# ADS7946.net
KiCad netlist of a schematic drawn in Altium Designer
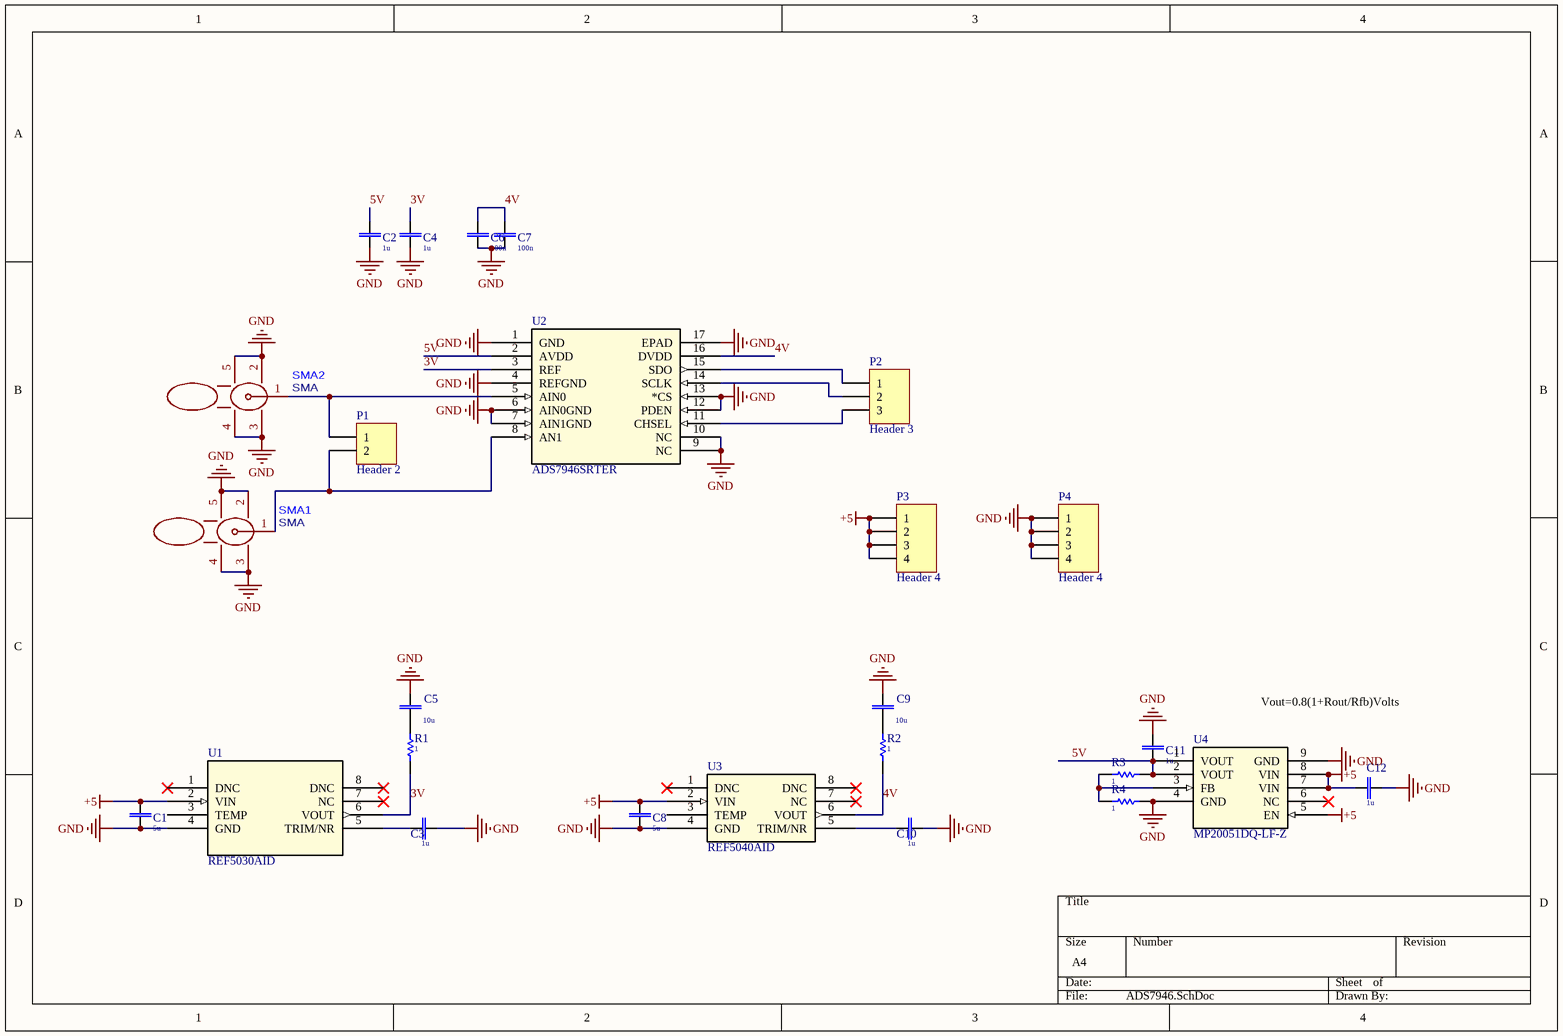
[diagram p0: ADS7946.SchDoc]

(export (version "E")
  (design (tool "Eeschema 10.0.6"))
  (components
    (comp (ref "C1")
      (value "5u")
      (footprint "0603")
      (description "Capacitor")
      (fields (field (name "Comment") "Cap") (field (name "PUBLISHER") "Altium Limited"))
      (libsource (lib "Miscellaneous Devices") (part "Cap"))
    )
    (comp (ref "C2")
      (value "1u")
      (footprint "0603")
      (description "Capacitor")
      (fields (field (name "Comment") "Cap") (field (name "PUBLISHER") "Altium Limited"))
      (libsource (lib "Miscellaneous Devices") (part "Cap"))
    )
    (comp (ref "C3")
      (value "1u")
      (footprint "0603")
      (description "Capacitor")
      (fields (field (name "Comment") "Cap") (field (name "PUBLISHER") "Altium Limited"))
      (libsource (lib "Miscellaneous Devices") (part "Cap"))
    )
    (comp (ref "C4")
      (value "1u")
      (footprint "0603")
      (description "Capacitor")
      (fields (field (name "Comment") "Cap") (field (name "PUBLISHER") "Altium Limited"))
      (libsource (lib "Miscellaneous Devices") (part "Cap"))
    )
    (comp (ref "C5")
      (value "10u")
      (footprint "0603")
      (description "Capacitor")
      (fields (field (name "Comment") "Cap") (field (name "PUBLISHER") "Altium Limited"))
      (libsource (lib "Miscellaneous Devices") (part "Cap"))
    )
    (comp (ref "C6")
      (value "100n")
      (footprint "0603")
      (description "Capacitor")
      (fields (field (name "Comment") "Cap") (field (name "PUBLISHER") "Altium Limited"))
      (libsource (lib "Miscellaneous Devices") (part "Cap"))
    )
    (comp (ref "C7")
      (value "100n")
      (footprint "0603")
      (description "Capacitor")
      (fields (field (name "Comment") "Cap") (field (name "PUBLISHER") "Altium Limited"))
      (libsource (lib "Miscellaneous Devices") (part "Cap"))
    )
    (comp (ref "C8")
      (value "5u")
      (footprint "0603")
      (description "Capacitor")
      (fields (field (name "Comment") "Cap") (field (name "PUBLISHER") "Altium Limited"))
      (libsource (lib "Miscellaneous Devices") (part "Cap"))
    )
    (comp (ref "C9")
      (value "10u")
      (footprint "0603")
      (description "Capacitor")
      (fields (field (name "Comment") "Cap") (field (name "PUBLISHER") "Altium Limited"))
      (libsource (lib "Miscellaneous Devices") (part "Cap"))
    )
    (comp (ref "C10")
      (value "1u")
      (footprint "0603")
      (description "Capacitor")
      (fields (field (name "Comment") "Cap") (field (name "PUBLISHER") "Altium Limited"))
      (libsource (lib "Miscellaneous Devices") (part "Cap"))
    )
    (comp (ref "C11")
      (value "1u")
      (footprint "0603")
      (description "Capacitor")
      (fields (field (name "Comment") "Cap") (field (name "PUBLISHER") "Altium Limited"))
      (libsource (lib "Miscellaneous Devices") (part "Cap"))
    )
    (comp (ref "C12")
      (value "1u")
      (footprint "0603")
      (description "Capacitor")
      (fields (field (name "Comment") "Cap") (field (name "PUBLISHER") "Altium Limited"))
      (libsource (lib "Miscellaneous Devices") (part "Cap"))
    )
    (comp (ref "P1")
      (value "Header 2")
      (footprint "HDR1X2")
      (description "Header, 2-Pin")
      (fields (field (name "PUBLISHER") "Altium Limited"))
      (libsource (lib "Miscellaneous Connectors") (part "Header 2"))
    )
    (comp (ref "P2")
      (value "Header 3")
      (footprint "HDR1X3")
      (description "Header, 3-Pin")
      (fields (field (name "PUBLISHER") "Altium Limited"))
      (libsource (lib "Miscellaneous Connectors") (part "Header 3"))
    )
    (comp (ref "P3")
      (value "Header 4")
      (footprint "HDR1X4")
      (description "Header, 4-Pin")
      (fields (field (name "PUBLISHER") "Altium Limited"))
      (libsource (lib "Miscellaneous Connectors") (part "Header 4"))
    )
    (comp (ref "P4")
      (value "Header 4")
      (footprint "HDR1X4")
      (description "Header, 4-Pin")
      (fields (field (name "PUBLISHER") "Altium Limited"))
      (libsource (lib "Miscellaneous Connectors") (part "Header 4"))
    )
    (comp (ref "R1")
      (value "1")
      (footprint "RES 0805N (2012)")
      (description "Resistor")
      (fields (field (name "PUBLISHER") "Altium Limited"))
      (libsource (lib "Miscellaneous Devices") (part "Res1"))
    )
    (comp (ref "R2")
      (value "1")
      (footprint "RES 0805N (2012)")
      (description "Resistor")
      (fields (field (name "PUBLISHER") "Altium Limited"))
      (libsource (lib "Miscellaneous Devices") (part "Res1"))
    )
    (comp (ref "R3")
      (value "1")
      (footprint "RES 0805N (2012)")
      (description "Resistor")
      (fields (field (name "PUBLISHER") "Altium Limited"))
      (libsource (lib "Miscellaneous Devices") (part "Res1"))
    )
    (comp (ref "R4")
      (value "1")
      (footprint "RES 0805N (2012)")
      (description "Resistor")
      (fields (field (name "PUBLISHER") "Altium Limited"))
      (libsource (lib "Miscellaneous Devices") (part "Res1"))
    )
    (comp (ref "SMA1") (value "SMA") (footprint "SMA-SMD_BWSMA-KE-P001") (libsource (lib "SMA") (part "SMA")))
    (comp (ref "SMA2") (value "SMA") (footprint "SMA-SMD_BWSMA-KE-P001") (libsource (lib "SMA") (part "SMA")))
    (comp (ref "U1")
      (value "REF5030AID")
      (footprint "D8")
      (description "No Description Available")
      (fields (field (name "COPYRIGHT") "Copyright (C) 2022 Ultra Librarian. All rights reserved."))
      (libsource (lib "REF5050AID") (part "REF5030AID"))
    )
    (comp (ref "U2")
      (value "ADS7946SRTER")
      (footprint "RTE16_1P7X1P7")
      (description "No Description Available")
      (fields (field (name "COPYRIGHT") "Copyright (C) 2022 Ultra Librarian. All rights reserved."))
      (libsource (lib "ADS7946SRTER") (part "ADS7946SRTER"))
    )
    (comp (ref "U3")
      (value "REF5040AID")
      (footprint "D8")
      (description "No Description Available")
      (fields (field (name "COPYRIGHT") "Copyright (C) 2022 Ultra Librarian. All rights reserved."))
      (libsource (lib "REF5050AID") (part "REF5040AID"))
    )
    (comp (ref "U4")
      (value "MP20051DQ-LF-Z")
      (footprint "QFN-8_MP20051_MNP")
      (description "No Description Available")
      (fields (field (name "COPYRIGHT") "Copyright (C) 2022 Ultra Librarian. All rights reserved."))
      (libsource (lib "ADS7946SRTER") (part "MP20051DQ-LF-Z"))
    )
  )
  (nets
    (net (code "1") (name "+5") (class "Default")
      (node (ref "C1") (pin "2") (pinfunction "2_2") (pintype "passive"))
      (node (ref "C12") (pin "2") (pinfunction "2_2") (pintype "passive"))
      (node (ref "C8") (pin "2") (pinfunction "2_2") (pintype "passive"))
      (node (ref "P3") (pin "1") (pinfunction "1_1") (pintype "passive"))
      (node (ref "P3") (pin "2") (pinfunction "2_2") (pintype "passive"))
      (node (ref "P3") (pin "3") (pinfunction "3_3") (pintype "passive"))
      (node (ref "P3") (pin "4") (pinfunction "4_4") (pintype "passive"))
      (node (ref "U1") (pin "2") (pinfunction "VIN_2") (pintype "input"))
      (node (ref "U3") (pin "2") (pinfunction "VIN_2") (pintype "input"))
      (node (ref "U4") (pin "5") (pinfunction "EN_5") (pintype "input"))
      (node (ref "U4") (pin "7") (pinfunction "VIN_7") (pintype "power_in"))
      (node (ref "U4") (pin "8") (pinfunction "VIN_8") (pintype "power_in"))
    )
    (net (code "2") (name "/3V") (class "Default")
      (node (ref "C4") (pin "2") (pinfunction "2_2") (pintype "passive"))
      (node (ref "R1") (pin "1") (pinfunction "1_1") (pintype "passive"))
      (node (ref "U1") (pin "6") (pinfunction "VOUT_6") (pintype "output"))
      (node (ref "U2") (pin "3") (pinfunction "REF_3") (pintype "power_in"))
    )
    (net (code "3") (name "/4V") (class "Default")
      (node (ref "C6") (pin "2") (pinfunction "2_2") (pintype "passive"))
      (node (ref "C7") (pin "2") (pinfunction "2_2") (pintype "passive"))
      (node (ref "R2") (pin "1") (pinfunction "1_1") (pintype "passive"))
      (node (ref "U2") (pin "16") (pinfunction "DVDD_16") (pintype "power_in"))
      (node (ref "U3") (pin "6") (pinfunction "VOUT_6") (pintype "output"))
    )
    (net (code "4") (name "/5V") (class "Default")
      (node (ref "C11") (pin "2") (pinfunction "2_2") (pintype "passive"))
      (node (ref "C2") (pin "2") (pinfunction "2_2") (pintype "passive"))
      (node (ref "R3") (pin "1") (pinfunction "1_1") (pintype "passive"))
      (node (ref "U2") (pin "2") (pinfunction "AVDD_2") (pintype "power_in"))
      (node (ref "U4") (pin "1") (pinfunction "VOUT_1") (pintype "power_in"))
      (node (ref "U4") (pin "2") (pinfunction "VOUT_2") (pintype "power_in"))
    )
    (net (code "5") (name "GND") (class "Default")
      (node (ref "C1") (pin "1") (pinfunction "1_1") (pintype "passive"))
      (node (ref "C10") (pin "2") (pinfunction "2_2") (pintype "passive"))
      (node (ref "C11") (pin "1") (pinfunction "1_1") (pintype "passive"))
      (node (ref "C12") (pin "1") (pinfunction "1_1") (pintype "passive"))
      (node (ref "C2") (pin "1") (pinfunction "1_1") (pintype "passive"))
      (node (ref "C3") (pin "2") (pinfunction "2_2") (pintype "passive"))
      (node (ref "C4") (pin "1") (pinfunction "1_1") (pintype "passive"))
      (node (ref "C5") (pin "2") (pinfunction "2_2") (pintype "passive"))
      (node (ref "C6") (pin "1") (pinfunction "1_1") (pintype "passive"))
      (node (ref "C7") (pin "1") (pinfunction "1_1") (pintype "passive"))
      (node (ref "C8") (pin "1") (pinfunction "1_1") (pintype "passive"))
      (node (ref "C9") (pin "2") (pinfunction "2_2") (pintype "passive"))
      (node (ref "P4") (pin "1") (pinfunction "1_1") (pintype "passive"))
      (node (ref "P4") (pin "2") (pinfunction "2_2") (pintype "passive"))
      (node (ref "P4") (pin "3") (pinfunction "3_3") (pintype "passive"))
      (node (ref "P4") (pin "4") (pinfunction "4_4") (pintype "passive"))
      (node (ref "R4") (pin "1") (pinfunction "1_1") (pintype "passive"))
      (node (ref "SMA1") (pin "2") (pinfunction "2_2") (pintype "passive"))
      (node (ref "SMA1") (pin "3") (pinfunction "3_3") (pintype "passive"))
      (node (ref "SMA1") (pin "4") (pinfunction "4_4") (pintype "passive"))
      (node (ref "SMA1") (pin "5") (pinfunction "5_5") (pintype "passive"))
      (node (ref "SMA2") (pin "2") (pinfunction "2_2") (pintype "passive"))
      (node (ref "SMA2") (pin "3") (pinfunction "3_3") (pintype "passive"))
      (node (ref "SMA2") (pin "4") (pinfunction "4_4") (pintype "passive"))
      (node (ref "SMA2") (pin "5") (pinfunction "5_5") (pintype "passive"))
      (node (ref "U1") (pin "4") (pinfunction "GND_4") (pintype "passive"))
      (node (ref "U2") (pin "1") (pinfunction "GND_1") (pintype "power_in"))
      (node (ref "U2") (pin "10") (pinfunction "NC_10") (pintype "passive"))
      (node (ref "U2") (pin "12") (pinfunction "PDEN_12") (pintype "input"))
      (node (ref "U2") (pin "13") (pinfunction "*CS_13") (pintype "input"))
      (node (ref "U2") (pin "17") (pinfunction "EPAD_17") (pintype "power_in"))
      (node (ref "U2") (pin "4") (pinfunction "REFGND_4") (pintype "power_in"))
      (node (ref "U2") (pin "6") (pinfunction "AIN0GND_6") (pintype "input"))
      (node (ref "U2") (pin "7") (pinfunction "AIN1GND_7") (pintype "input"))
      (node (ref "U2") (pin "9") (pinfunction "NC_9") (pintype "passive"))
      (node (ref "U3") (pin "4") (pinfunction "GND_4") (pintype "passive"))
      (node (ref "U4") (pin "4") (pinfunction "GND_4") (pintype "power_in"))
      (node (ref "U4") (pin "9") (pinfunction "GND_9") (pintype "power_in"))
    )
    (net (code "6") (name "Net-(C5-Pad1)") (class "Default")
      (node (ref "C5") (pin "1") (pinfunction "1_1") (pintype "passive"))
      (node (ref "R1") (pin "2") (pinfunction "2_2") (pintype "passive"))
    )
    (net (code "7") (name "Net-(C9-Pad1)") (class "Default")
      (node (ref "C9") (pin "1") (pinfunction "1_1") (pintype "passive"))
      (node (ref "R2") (pin "2") (pinfunction "2_2") (pintype "passive"))
    )
    (net (code "8") (name "Net-(U1-TRIM{slash}NR)") (class "Default")
      (node (ref "C3") (pin "1") (pinfunction "1_1") (pintype "passive"))
      (node (ref "U1") (pin "5") (pinfunction "TRIM/NR_5") (pintype "passive"))
    )
    (net (code "9") (name "Net-(U2-AIN0)") (class "Default")
      (node (ref "P1") (pin "1") (pinfunction "1_1") (pintype "passive"))
      (node (ref "SMA2") (pin "1") (pinfunction "1_1") (pintype "passive"))
      (node (ref "U2") (pin "5") (pinfunction "AIN0_5") (pintype "input"))
    )
    (net (code "10") (name "Net-(U2-AN1)") (class "Default")
      (node (ref "P1") (pin "2") (pinfunction "2_2") (pintype "passive"))
      (node (ref "SMA1") (pin "1") (pinfunction "1_1") (pintype "passive"))
      (node (ref "U2") (pin "8") (pinfunction "AN1_8") (pintype "input"))
    )
    (net (code "11") (name "Net-(U2-CHSEL)") (class "Default")
      (node (ref "P2") (pin "3") (pinfunction "3_3") (pintype "passive"))
      (node (ref "U2") (pin "11") (pinfunction "CHSEL_11") (pintype "input"))
    )
    (net (code "12") (name "Net-(U2-SCLK)") (class "Default")
      (node (ref "P2") (pin "2") (pinfunction "2_2") (pintype "passive"))
      (node (ref "U2") (pin "14") (pinfunction "SCLK_14") (pintype "input"))
    )
    (net (code "13") (name "Net-(U2-SDO)") (class "Default")
      (node (ref "P2") (pin "1") (pinfunction "1_1") (pintype "passive"))
      (node (ref "U2") (pin "15") (pinfunction "SDO_15") (pintype "output"))
    )
    (net (code "14") (name "Net-(U3-TRIM{slash}NR)") (class "Default")
      (node (ref "C10") (pin "1") (pinfunction "1_1") (pintype "passive"))
      (node (ref "U3") (pin "5") (pinfunction "TRIM/NR_5") (pintype "passive"))
    )
    (net (code "15") (name "Net-(U4-FB)") (class "Default")
      (node (ref "R3") (pin "2") (pinfunction "2_2") (pintype "passive"))
      (node (ref "R4") (pin "2") (pinfunction "2_2") (pintype "passive"))
      (node (ref "U4") (pin "3") (pinfunction "FB_3") (pintype "input"))
    )
    (net (code "16") (name "unconnected-(U1-DNC-Pad1)") (class "Default")
      (node (ref "U1") (pin "1") (pinfunction "DNC_1") (pintype "passive+no_connect"))
    )
    (net (code "17") (name "unconnected-(U1-DNC-Pad8)") (class "Default")
      (node (ref "U1") (pin "8") (pinfunction "DNC_8") (pintype "passive+no_connect"))
    )
    (net (code "18") (name "unconnected-(U1-NC-Pad7)") (class "Default")
      (node (ref "U1") (pin "7") (pinfunction "NC_7") (pintype "passive+no_connect"))
    )
    (net (code "19") (name "unconnected-(U1-TEMP-Pad3)") (class "Default")
      (node (ref "U1") (pin "3") (pinfunction "TEMP_3") (pintype "passive"))
    )
    (net (code "20") (name "unconnected-(U3-DNC-Pad1)") (class "Default")
      (node (ref "U3") (pin "1") (pinfunction "DNC_1") (pintype "passive+no_connect"))
    )
    (net (code "21") (name "unconnected-(U3-DNC-Pad8)") (class "Default")
      (node (ref "U3") (pin "8") (pinfunction "DNC_8") (pintype "passive+no_connect"))
    )
    (net (code "22") (name "unconnected-(U3-NC-Pad7)") (class "Default")
      (node (ref "U3") (pin "7") (pinfunction "NC_7") (pintype "passive+no_connect"))
    )
    (net (code "23") (name "unconnected-(U3-TEMP-Pad3)") (class "Default")
      (node (ref "U3") (pin "3") (pinfunction "TEMP_3") (pintype "passive"))
    )
    (net (code "24") (name "unconnected-(U4-NC-Pad6)") (class "Default")
      (node (ref "U4") (pin "6") (pinfunction "NC_6") (pintype "passive+no_connect"))
    )
  )
)
